# MiniConnectorBoard.net
KiCad netlist of a schematic drawn in EAGLE
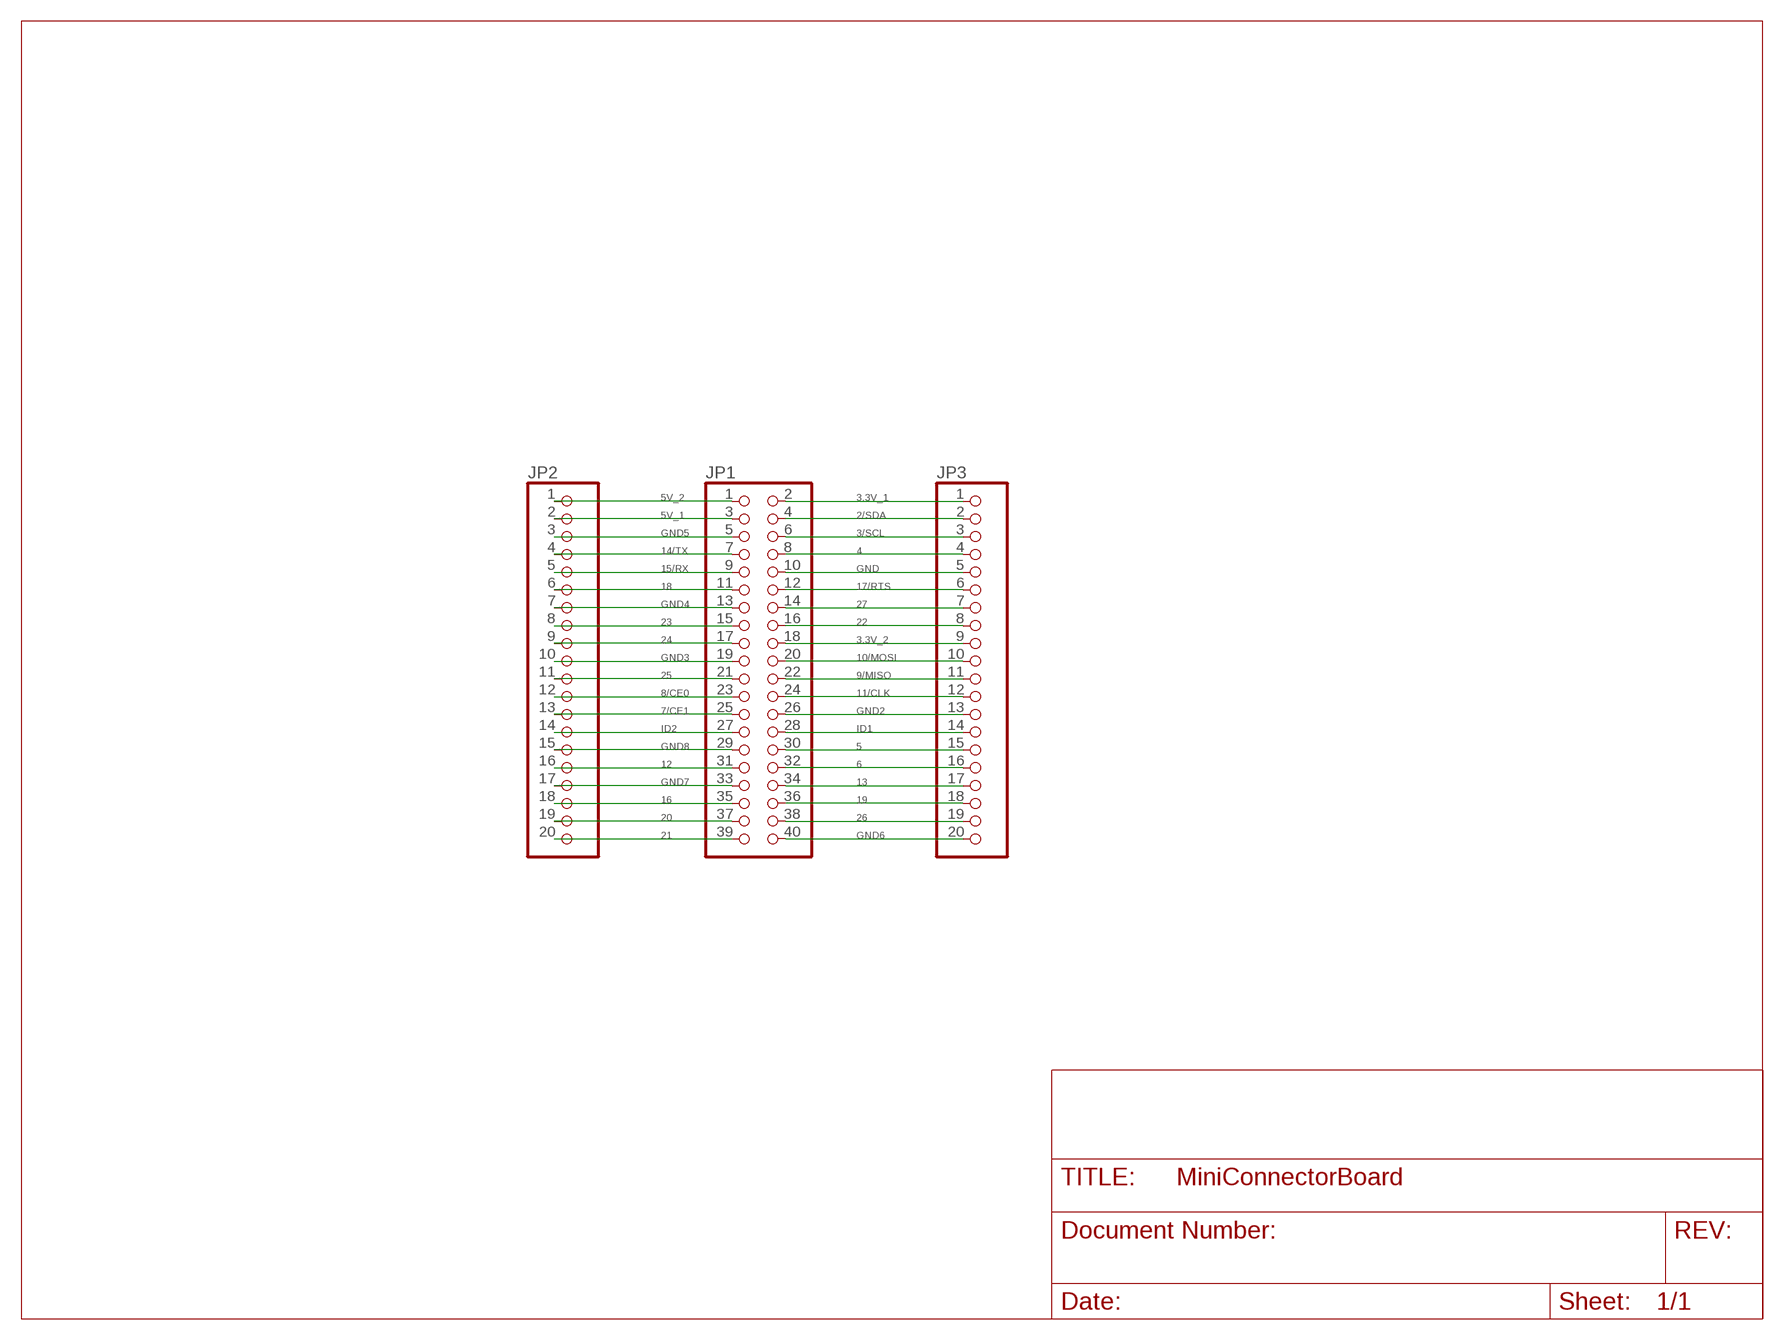
[diagram p0: schematic, sheet 1]

(export (version "E")
  (design (tool "Eeschema 10.0.6"))
  (components
    (comp (ref "JP1")
      (value "NONE")
      (footprint "eagle-import:2X20")
      (libsource (lib "eagle-import") (part "PINHD-2X20"))
    )
    (comp (ref "JP2")
      (value "NONE")
      (footprint "eagle-import:1X20")
      (libsource (lib "eagle-import") (part "PINHD-1X20"))
    )
    (comp (ref "JP3")
      (value "NONE")
      (footprint "eagle-import:1X20")
      (libsource (lib "eagle-import") (part "PINHD-1X20"))
    )
  )
  (nets
    (net (code "1") (name "/2{slash}SDA") (class "Default")
      (node (ref "JP1") (pin "4") (pinfunction "4_4") (pintype "passive"))
      (node (ref "JP3") (pin "2") (pinfunction "2_2") (pintype "passive"))
    )
    (net (code "2") (name "/3.3V_1") (class "Default")
      (node (ref "JP1") (pin "2") (pinfunction "2_2") (pintype "passive"))
      (node (ref "JP3") (pin "1") (pinfunction "1_1") (pintype "passive"))
    )
    (net (code "3") (name "/3.3V_2") (class "Default")
      (node (ref "JP1") (pin "18") (pinfunction "18_18") (pintype "passive"))
      (node (ref "JP3") (pin "9") (pinfunction "9_9") (pintype "passive"))
    )
    (net (code "4") (name "/3{slash}SCL") (class "Default")
      (node (ref "JP1") (pin "6") (pinfunction "6_6") (pintype "passive"))
      (node (ref "JP3") (pin "3") (pinfunction "3_3") (pintype "passive"))
    )
    (net (code "5") (name "/4") (class "Default")
      (node (ref "JP1") (pin "8") (pinfunction "8_8") (pintype "passive"))
      (node (ref "JP3") (pin "4") (pinfunction "4_4") (pintype "passive"))
    )
    (net (code "6") (name "/5") (class "Default")
      (node (ref "JP1") (pin "30") (pinfunction "30_30") (pintype "passive"))
      (node (ref "JP3") (pin "15") (pinfunction "15_15") (pintype "passive"))
    )
    (net (code "7") (name "/5V_1") (class "Default")
      (node (ref "JP1") (pin "3") (pinfunction "3_3") (pintype "passive"))
      (node (ref "JP2") (pin "2") (pinfunction "2_2") (pintype "passive"))
    )
    (net (code "8") (name "/5V_2") (class "Default")
      (node (ref "JP1") (pin "1") (pinfunction "1_1") (pintype "passive"))
      (node (ref "JP2") (pin "1") (pinfunction "1_1") (pintype "passive"))
    )
    (net (code "9") (name "/6") (class "Default")
      (node (ref "JP1") (pin "32") (pinfunction "32_32") (pintype "passive"))
      (node (ref "JP3") (pin "16") (pinfunction "16_16") (pintype "passive"))
    )
    (net (code "10") (name "/7{slash}CE1") (class "Default")
      (node (ref "JP1") (pin "25") (pinfunction "25_25") (pintype "passive"))
      (node (ref "JP2") (pin "13") (pinfunction "13_13") (pintype "passive"))
    )
    (net (code "11") (name "/8{slash}CE0") (class "Default")
      (node (ref "JP1") (pin "23") (pinfunction "23_23") (pintype "passive"))
      (node (ref "JP2") (pin "12") (pinfunction "12_12") (pintype "passive"))
    )
    (net (code "12") (name "/9{slash}MISO") (class "Default")
      (node (ref "JP1") (pin "22") (pinfunction "22_22") (pintype "passive"))
      (node (ref "JP3") (pin "11") (pinfunction "11_11") (pintype "passive"))
    )
    (net (code "13") (name "/10{slash}MOSI") (class "Default")
      (node (ref "JP1") (pin "20") (pinfunction "20_20") (pintype "passive"))
      (node (ref "JP3") (pin "10") (pinfunction "10_10") (pintype "passive"))
    )
    (net (code "14") (name "/11{slash}CLK") (class "Default")
      (node (ref "JP1") (pin "24") (pinfunction "24_24") (pintype "passive"))
      (node (ref "JP3") (pin "12") (pinfunction "12_12") (pintype "passive"))
    )
    (net (code "15") (name "/12") (class "Default")
      (node (ref "JP1") (pin "31") (pinfunction "31_31") (pintype "passive"))
      (node (ref "JP2") (pin "16") (pinfunction "16_16") (pintype "passive"))
    )
    (net (code "16") (name "/13") (class "Default")
      (node (ref "JP1") (pin "34") (pinfunction "34_34") (pintype "passive"))
      (node (ref "JP3") (pin "17") (pinfunction "17_17") (pintype "passive"))
    )
    (net (code "17") (name "/14{slash}TX") (class "Default")
      (node (ref "JP1") (pin "7") (pinfunction "7_7") (pintype "passive"))
      (node (ref "JP2") (pin "4") (pinfunction "4_4") (pintype "passive"))
    )
    (net (code "18") (name "/15{slash}RX") (class "Default")
      (node (ref "JP1") (pin "9") (pinfunction "9_9") (pintype "passive"))
      (node (ref "JP2") (pin "5") (pinfunction "5_5") (pintype "passive"))
    )
    (net (code "19") (name "/16") (class "Default")
      (node (ref "JP1") (pin "35") (pinfunction "35_35") (pintype "passive"))
      (node (ref "JP2") (pin "18") (pinfunction "18_18") (pintype "passive"))
    )
    (net (code "20") (name "/17{slash}RTS") (class "Default")
      (node (ref "JP1") (pin "12") (pinfunction "12_12") (pintype "passive"))
      (node (ref "JP3") (pin "6") (pinfunction "6_6") (pintype "passive"))
    )
    (net (code "21") (name "/18") (class "Default")
      (node (ref "JP1") (pin "11") (pinfunction "11_11") (pintype "passive"))
      (node (ref "JP2") (pin "6") (pinfunction "6_6") (pintype "passive"))
    )
    (net (code "22") (name "/19") (class "Default")
      (node (ref "JP1") (pin "36") (pinfunction "36_36") (pintype "passive"))
      (node (ref "JP3") (pin "18") (pinfunction "18_18") (pintype "passive"))
    )
    (net (code "23") (name "/20") (class "Default")
      (node (ref "JP1") (pin "37") (pinfunction "37_37") (pintype "passive"))
      (node (ref "JP2") (pin "19") (pinfunction "19_19") (pintype "passive"))
    )
    (net (code "24") (name "/21") (class "Default")
      (node (ref "JP1") (pin "39") (pinfunction "39_39") (pintype "passive"))
      (node (ref "JP2") (pin "20") (pinfunction "20_20") (pintype "passive"))
    )
    (net (code "25") (name "/22") (class "Default")
      (node (ref "JP1") (pin "16") (pinfunction "16_16") (pintype "passive"))
      (node (ref "JP3") (pin "8") (pinfunction "8_8") (pintype "passive"))
    )
    (net (code "26") (name "/23") (class "Default")
      (node (ref "JP1") (pin "15") (pinfunction "15_15") (pintype "passive"))
      (node (ref "JP2") (pin "8") (pinfunction "8_8") (pintype "passive"))
    )
    (net (code "27") (name "/24") (class "Default")
      (node (ref "JP1") (pin "17") (pinfunction "17_17") (pintype "passive"))
      (node (ref "JP2") (pin "9") (pinfunction "9_9") (pintype "passive"))
    )
    (net (code "28") (name "/25") (class "Default")
      (node (ref "JP1") (pin "21") (pinfunction "21_21") (pintype "passive"))
      (node (ref "JP2") (pin "11") (pinfunction "11_11") (pintype "passive"))
    )
    (net (code "29") (name "/26") (class "Default")
      (node (ref "JP1") (pin "38") (pinfunction "38_38") (pintype "passive"))
      (node (ref "JP3") (pin "19") (pinfunction "19_19") (pintype "passive"))
    )
    (net (code "30") (name "/27") (class "Default")
      (node (ref "JP1") (pin "14") (pinfunction "14_14") (pintype "passive"))
      (node (ref "JP3") (pin "7") (pinfunction "7_7") (pintype "passive"))
    )
    (net (code "31") (name "/GND") (class "Default")
      (node (ref "JP1") (pin "10") (pinfunction "10_10") (pintype "passive"))
      (node (ref "JP3") (pin "5") (pinfunction "5_5") (pintype "passive"))
    )
    (net (code "32") (name "/GND2") (class "Default")
      (node (ref "JP1") (pin "26") (pinfunction "26_26") (pintype "passive"))
      (node (ref "JP3") (pin "13") (pinfunction "13_13") (pintype "passive"))
    )
    (net (code "33") (name "/GND3") (class "Default")
      (node (ref "JP1") (pin "19") (pinfunction "19_19") (pintype "passive"))
      (node (ref "JP2") (pin "10") (pinfunction "10_10") (pintype "passive"))
    )
    (net (code "34") (name "/GND4") (class "Default")
      (node (ref "JP1") (pin "13") (pinfunction "13_13") (pintype "passive"))
      (node (ref "JP2") (pin "7") (pinfunction "7_7") (pintype "passive"))
    )
    (net (code "35") (name "/GND5") (class "Default")
      (node (ref "JP1") (pin "5") (pinfunction "5_5") (pintype "passive"))
      (node (ref "JP2") (pin "3") (pinfunction "3_3") (pintype "passive"))
    )
    (net (code "36") (name "/GND6") (class "Default")
      (node (ref "JP1") (pin "40") (pinfunction "40_40") (pintype "passive"))
      (node (ref "JP3") (pin "20") (pinfunction "20_20") (pintype "passive"))
    )
    (net (code "37") (name "/GND7") (class "Default")
      (node (ref "JP1") (pin "33") (pinfunction "33_33") (pintype "passive"))
      (node (ref "JP2") (pin "17") (pinfunction "17_17") (pintype "passive"))
    )
    (net (code "38") (name "/GND8") (class "Default")
      (node (ref "JP1") (pin "29") (pinfunction "29_29") (pintype "passive"))
      (node (ref "JP2") (pin "15") (pinfunction "15_15") (pintype "passive"))
    )
    (net (code "39") (name "/ID1") (class "Default")
      (node (ref "JP1") (pin "28") (pinfunction "28_28") (pintype "passive"))
      (node (ref "JP3") (pin "14") (pinfunction "14_14") (pintype "passive"))
    )
    (net (code "40") (name "/ID2") (class "Default")
      (node (ref "JP1") (pin "27") (pinfunction "27_27") (pintype "passive"))
      (node (ref "JP2") (pin "14") (pinfunction "14_14") (pintype "passive"))
    )
  )
)
